# ldr.net
KiCad netlist of a schematic drawn in EAGLE
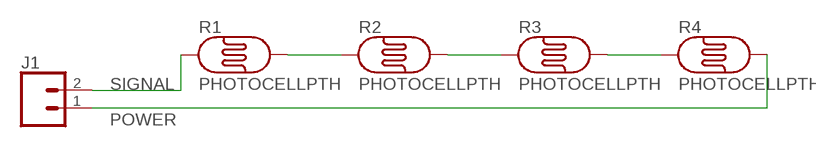
[diagram p0: schematic, sheet 1]

(export (version "E")
  (design (tool "Eeschema 10.0.6"))
  (components
    (comp (ref "J1")
      (value "CONN_02")
      (footprint "eagle-import:1X02")
      (libsource (lib "eagle-import") (part "CONN_02"))
    )
    (comp (ref "R1")
      (value "PHOTOCELLPTH")
      (footprint "eagle-import:PHOTOCELL")
      (libsource (lib "eagle-import") (part "PHOTOCELLPTH"))
    )
    (comp (ref "R2")
      (value "PHOTOCELLPTH")
      (footprint "eagle-import:PHOTOCELL")
      (libsource (lib "eagle-import") (part "PHOTOCELLPTH"))
    )
    (comp (ref "R3")
      (value "PHOTOCELLPTH")
      (footprint "eagle-import:PHOTOCELL")
      (libsource (lib "eagle-import") (part "PHOTOCELLPTH"))
    )
    (comp (ref "R4")
      (value "PHOTOCELLPTH")
      (footprint "eagle-import:PHOTOCELL")
      (libsource (lib "eagle-import") (part "PHOTOCELLPTH"))
    )
  )
  (nets
    (net (code "1") (name "/POWER") (class "Default")
      (node (ref "J1") (pin "1") (pinfunction "1_1") (pintype "passive"))
      (node (ref "R4") (pin "2") (pinfunction "P$2_2") (pintype "bidirectional"))
    )
    (net (code "2") (name "/SIGNAL") (class "Default")
      (node (ref "J1") (pin "2") (pinfunction "2_2") (pintype "passive"))
      (node (ref "R1") (pin "1") (pinfunction "P$1_1") (pintype "bidirectional"))
    )
    (net (code "3") (name "Net-(R1-P$2)") (class "Default")
      (node (ref "R1") (pin "2") (pinfunction "P$2_2") (pintype "bidirectional"))
      (node (ref "R2") (pin "1") (pinfunction "P$1_1") (pintype "bidirectional"))
    )
    (net (code "4") (name "Net-(R2-P$2)") (class "Default")
      (node (ref "R2") (pin "2") (pinfunction "P$2_2") (pintype "bidirectional"))
      (node (ref "R3") (pin "1") (pinfunction "P$1_1") (pintype "bidirectional"))
    )
    (net (code "5") (name "Net-(R3-P$2)") (class "Default")
      (node (ref "R3") (pin "2") (pinfunction "P$2_2") (pintype "bidirectional"))
      (node (ref "R4") (pin "1") (pinfunction "P$1_1") (pintype "bidirectional"))
    )
  )
)
